# design.net
KiCad netlist of a schematic drawn in EasyEDA Pro
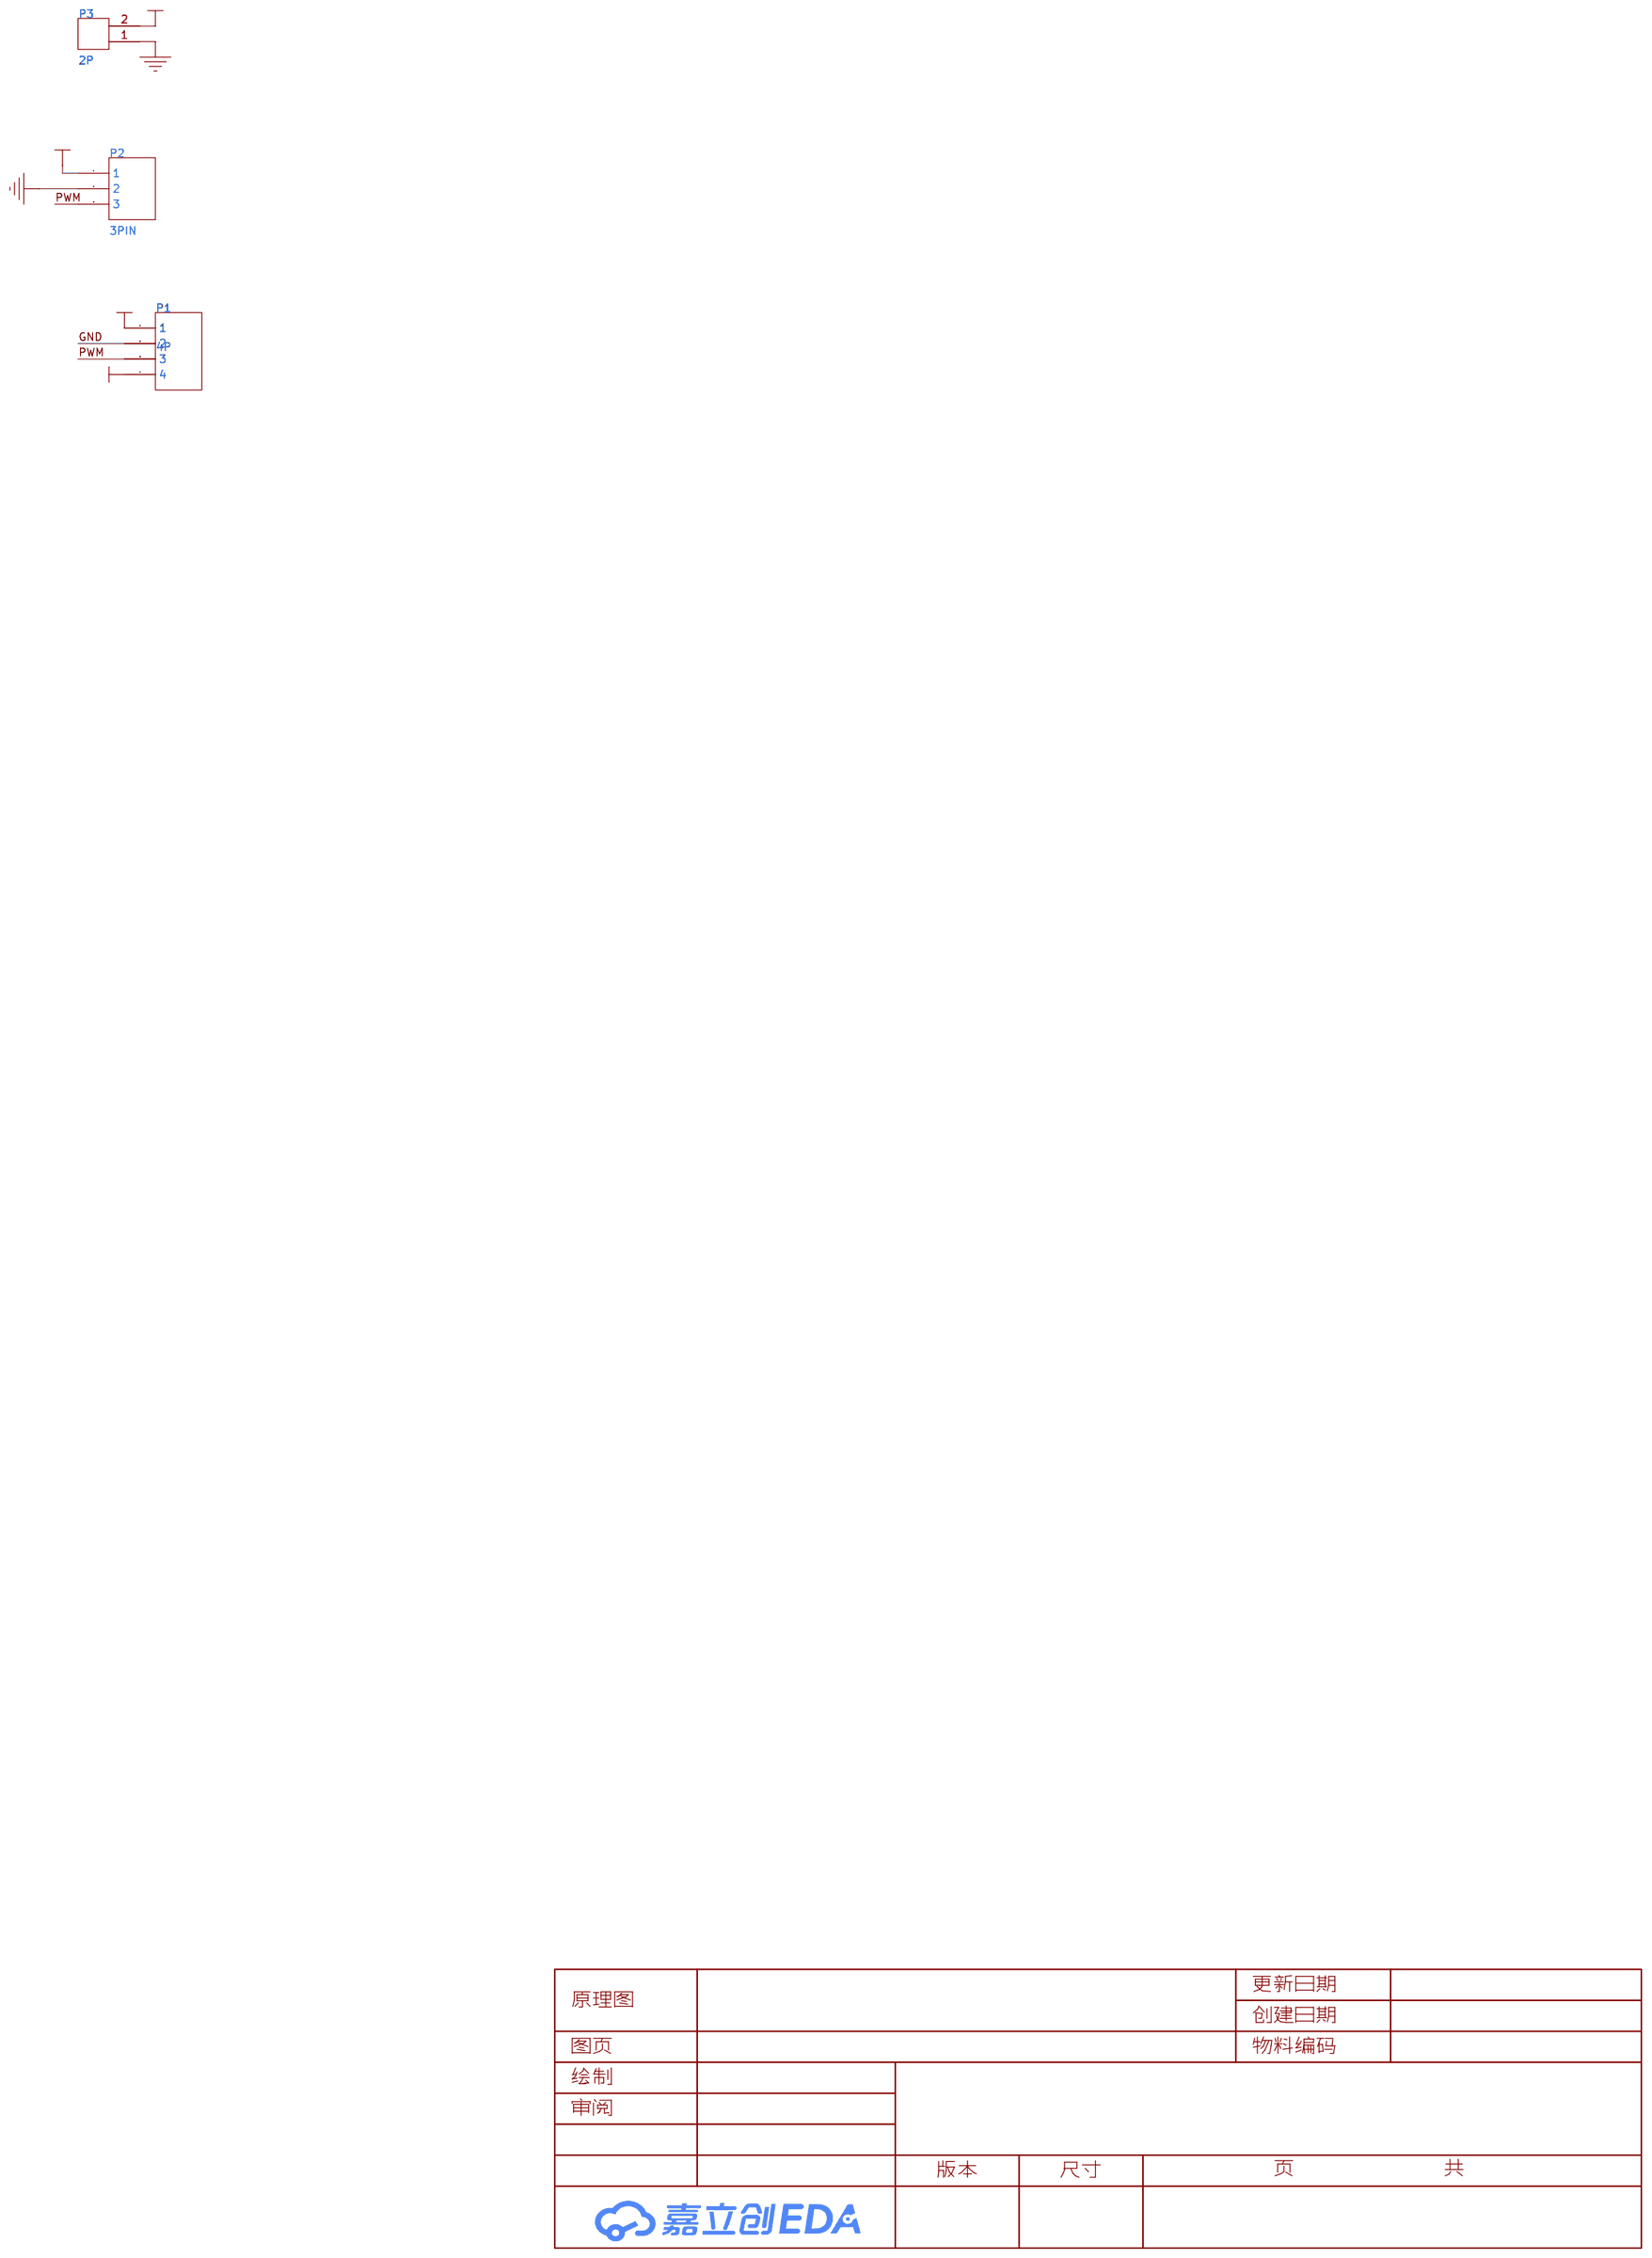
[diagram p0: schematic sheet]

(export (version "E")
  (design (tool "Eeschema 10.0.6"))
  (components
    (comp (ref "P1") (value "4P") (footprint "easyedapro:SIP4") (libsource (lib "easyedapro") (part "4P")))
    (comp (ref "P2")
      (value "3PIN")
      (footprint "easyedapro:HDR1X3_P")
      (libsource (lib "easyedapro") (part "3P"))
    )
    (comp (ref "P3")
      (value "2P")
      (footprint "easyedapro:HDR1X2_P")
      (libsource (lib "easyedapro") (part "2P"))
    )
  )
  (nets
    (net (code "1") (name "/PWM") (class "Default")
      (node (ref "P1") (pin "3") (pinfunction "3_3") (pintype "unspecified"))
      (node (ref "P2") (pin "3") (pinfunction "3_3") (pintype "unspecified"))
    )
    (net (code "2") (name "12V") (class "Default")
      (node (ref "P1") (pin "4") (pinfunction "4_4") (pintype "unspecified"))
      (node (ref "P2") (pin "1") (pinfunction "1_1") (pintype "unspecified"))
    )
    (net (code "3") (name "48V") (class "Default")
      (node (ref "P1") (pin "1") (pinfunction "1_1") (pintype "unspecified"))
      (node (ref "P3") (pin "2") (pintype "unspecified"))
    )
    (net (code "4") (name "GND") (class "Default")
      (node (ref "P1") (pin "2") (pinfunction "2_2") (pintype "unspecified"))
      (node (ref "P2") (pin "2") (pinfunction "2_2") (pintype "unspecified"))
      (node (ref "P3") (pin "1") (pintype "unspecified"))
    )
  )
)
